# 07_Buzzer.net
KiCad netlist of a schematic drawn in Altium Designer
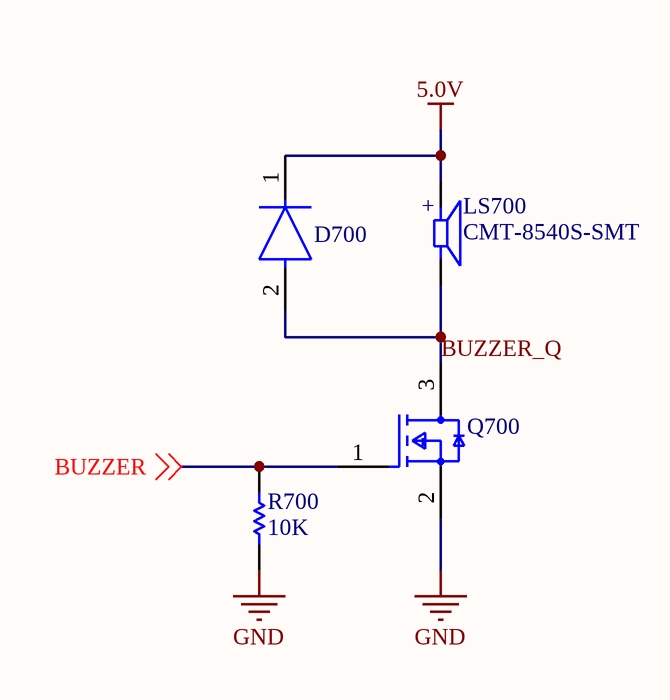
[diagram p0: 07_Buzzer.SchDoc]

(export (version "E")
  (design (tool "Eeschema 10.0.6"))
  (components
    (comp (ref "D700")
      (value "CGRM4004-G")
      (footprint "Diodes_SOD123_IPC_A")
      (description "DIODE GEN PURP 400V 1A MINISMA")
      (libsource (lib "Diodes") (part "CGRM4004-G"))
    )
    (comp (ref "LS700")
      (value "CMT-8540S-SMT")
      (footprint "CUI_CMT-8540S-SMT")
      (description "AUDIO MAGNETIC XDCR 1-6V SMD")
      (fields (field (name "MF") "CUI Devices") (field (name "MP") "CMT-8540S-SMT-TR"))
      (libsource (lib "Buzzer") (part "CMT-8540S-SMT"))
    )
    (comp (ref "Q700")
      (value "DMN6140L-13")
      (footprint "Diodes_Inc_SOT23_IPC_A")
      (description "MOSFET N-CH 60V 300MA SOT23-3")
      (libsource (lib "Transistors") (part "DMN6140L-13"))
    )
    (comp (ref "R700")
      (value "RES_0805_K_010.00")
      (footprint "RES_0805")
      (description "RES 10K 1/10W 1% 0805 SMD")
      (fields (field (name "TOLERANCE") "1%") (field (name "RESISTANCE") "10K"))
      (libsource (lib "Resistors") (part "RES_0805_K_010.00"))
    )
  )
  (nets
    (net (code "1") (name "/BUZZER_Q") (class "Default")
      (node (ref "D700") (pin "2") (pinfunction "A_2") (pintype "passive"))
      (node (ref "LS700") (pin "N") (pinfunction "N_N") (pintype "passive"))
      (node (ref "Q700") (pin "3") (pinfunction "D_3") (pintype "passive"))
    )
    (net (code "2") (name "5.0V") (class "Default")
      (node (ref "D700") (pin "1") (pinfunction "C_1") (pintype "passive"))
      (node (ref "LS700") (pin "P") (pinfunction "P_P") (pintype "passive"))
    )
    (net (code "3") (name "BUZZER") (class "Default")
      (node (ref "Q700") (pin "1") (pinfunction "G_1") (pintype "passive"))
      (node (ref "R700") (pin "2") (pinfunction "2_2") (pintype "passive"))
    )
    (net (code "4") (name "GND") (class "Default")
      (node (ref "Q700") (pin "2") (pinfunction "S_2") (pintype "passive"))
      (node (ref "R700") (pin "1") (pinfunction "1_1") (pintype "passive"))
    )
  )
)
